# Decoder_35.net
KiCad netlist of a schematic drawn in EAGLE
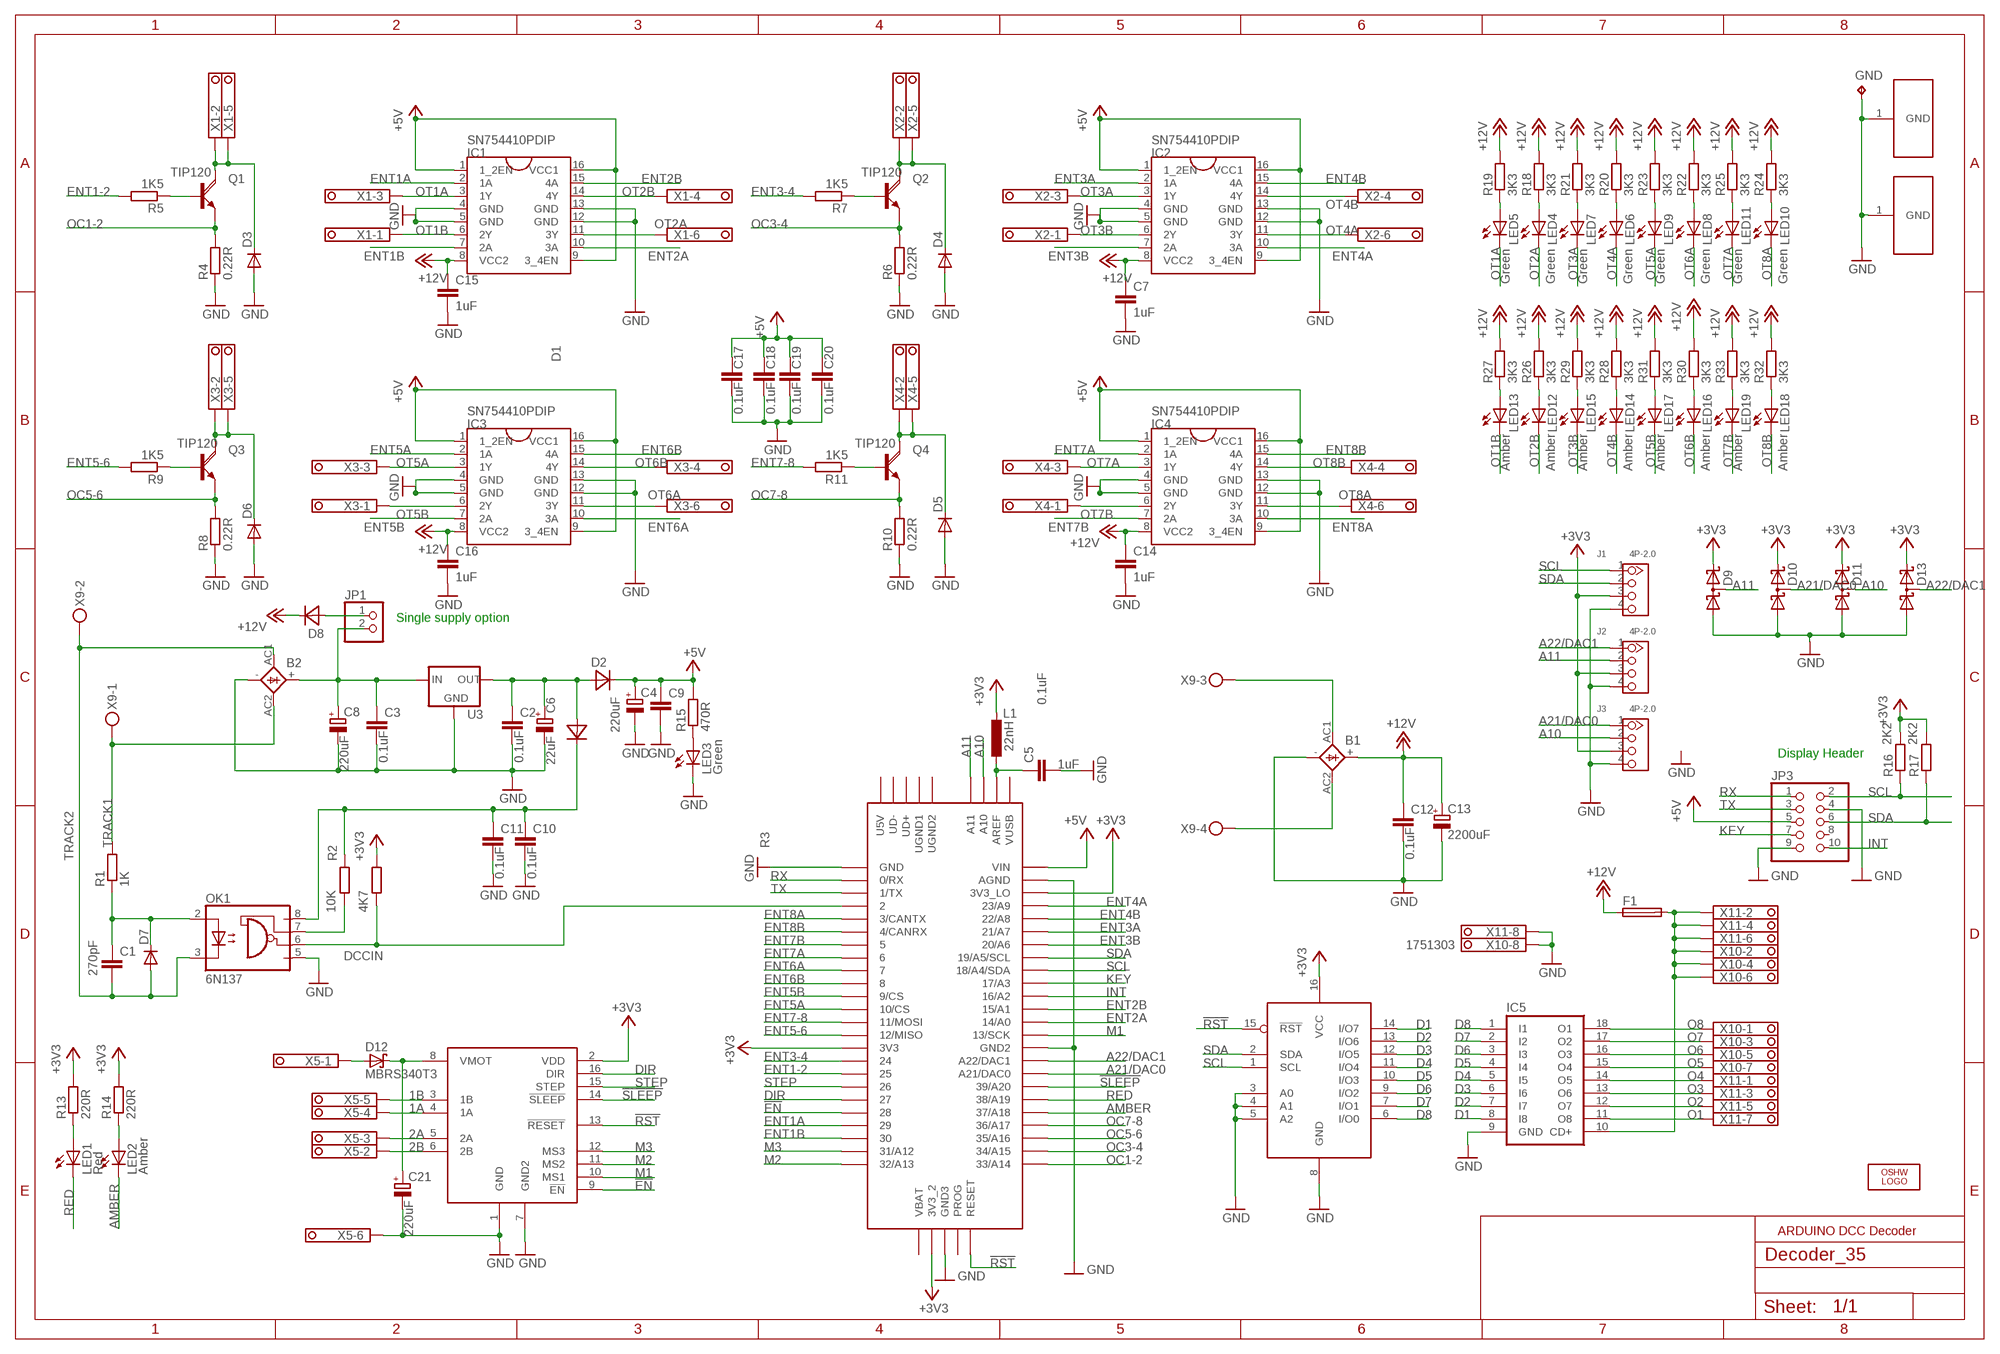
[diagram p0: schematic, sheet 1]

(export (version "E")
  (design (tool "Eeschema 10.0.6"))
  (components
    (comp (ref "B1")
      (value "FB15A")
      (footprint "eagle-import:FB15A")
      (libsource (lib "eagle-import") (part "FB15A"))
    )
    (comp (ref "B2")
      (value "FB15A")
      (footprint "eagle-import:FB15A")
      (libsource (lib "eagle-import") (part "FB15A"))
    )
    (comp (ref "C1")
      (value "270pF")
      (footprint "eagle-import:C0805")
      (libsource (lib "eagle-import") (part "C-EUC0805"))
    )
    (comp (ref "C2")
      (value "0.1uF")
      (footprint "eagle-import:C0805")
      (libsource (lib "eagle-import") (part "C-EUC0805"))
    )
    (comp (ref "C3")
      (value "0.1uF")
      (footprint "eagle-import:C0805")
      (libsource (lib "eagle-import") (part "C-EUC0805"))
    )
    (comp (ref "C4")
      (value "220uF")
      (footprint "eagle-import:E2,5-5")
      (libsource (lib "eagle-import") (part "CPOL-EUE2.5-5"))
    )
    (comp (ref "C5")
      (value "1uF")
      (footprint "eagle-import:C0805")
      (libsource (lib "eagle-import") (part "C-EUC0805"))
    )
    (comp (ref "C6")
      (value "22uF")
      (footprint "eagle-import:E2,5-5")
      (libsource (lib "eagle-import") (part "CPOL-EUE2.5-5"))
    )
    (comp (ref "C7")
      (value "1uF")
      (footprint "eagle-import:C0805")
      (libsource (lib "eagle-import") (part "C-EUC0805"))
    )
    (comp (ref "C8")
      (value "220uF")
      (footprint "eagle-import:E5-8,5")
      (libsource (lib "eagle-import") (part "CPOL-EUE5-8.5"))
    )
    (comp (ref "C9")
      (value "0.1uF")
      (footprint "eagle-import:C0805")
      (libsource (lib "eagle-import") (part "C-EUC0805"))
    )
    (comp (ref "C10")
      (value "0.1uF")
      (footprint "eagle-import:C0805")
      (libsource (lib "eagle-import") (part "C-EUC0805"))
    )
    (comp (ref "C11")
      (value "0.1uF")
      (footprint "eagle-import:C0805")
      (libsource (lib "eagle-import") (part "C-EUC0805"))
    )
    (comp (ref "C12")
      (value "0.1uF")
      (footprint "eagle-import:C0805")
      (libsource (lib "eagle-import") (part "C-EUC0805"))
    )
    (comp (ref "C13")
      (value "2200uF")
      (footprint "eagle-import:E5-13")
      (libsource (lib "eagle-import") (part "CPOL-EUE5-13"))
    )
    (comp (ref "C14")
      (value "1uF")
      (footprint "eagle-import:C0805")
      (libsource (lib "eagle-import") (part "C-EUC0805"))
    )
    (comp (ref "C15")
      (value "1uF")
      (footprint "eagle-import:C0805")
      (libsource (lib "eagle-import") (part "C-EUC0805"))
    )
    (comp (ref "C16")
      (value "1uF")
      (footprint "eagle-import:C0805")
      (libsource (lib "eagle-import") (part "C-EUC0805"))
    )
    (comp (ref "C17")
      (value "0.1uF")
      (footprint "eagle-import:C0805")
      (libsource (lib "eagle-import") (part "C-EUC0805"))
    )
    (comp (ref "C18")
      (value "0.1uF")
      (footprint "eagle-import:C0805")
      (libsource (lib "eagle-import") (part "C-EUC0805"))
    )
    (comp (ref "C19")
      (value "0.1uF")
      (footprint "eagle-import:C0805")
      (libsource (lib "eagle-import") (part "C-EUC0805"))
    )
    (comp (ref "C20")
      (value "0.1uF")
      (footprint "eagle-import:C0805")
      (libsource (lib "eagle-import") (part "C-EUC0805"))
    )
    (comp (ref "C21")
      (value "220uF")
      (footprint "eagle-import:E5-8,5")
      (libsource (lib "eagle-import") (part "CPOL-EUE5-8.5"))
    )
    (comp (ref "D1")
      (value "MBRA340T3")
      (footprint "eagle-import:SMA")
      (libsource (lib "eagle-import") (part "MBRA340T3"))
    )
    (comp (ref "D2")
      (value "MBRA340T3")
      (footprint "eagle-import:SMA")
      (libsource (lib "eagle-import") (part "MBRA340T3"))
    )
    (comp (ref "D3")
      (value "CGRM4002-G")
      (footprint "eagle-import:SOD-123_MINI-SMA")
      (libsource (lib "eagle-import") (part "CGRM400-G2"))
    )
    (comp (ref "D4")
      (value "CGRM4002-G")
      (footprint "eagle-import:SOD-123_MINI-SMA")
      (libsource (lib "eagle-import") (part "CGRM400-G2"))
    )
    (comp (ref "D5")
      (value "CGRM4002-G")
      (footprint "eagle-import:SOD-123_MINI-SMA")
      (libsource (lib "eagle-import") (part "CGRM400-G2"))
    )
    (comp (ref "D6")
      (value "CGRM4002-G")
      (footprint "eagle-import:SOD-123_MINI-SMA")
      (libsource (lib "eagle-import") (part "CGRM400-G2"))
    )
    (comp (ref "D7")
      (value "CGRM4002-G")
      (footprint "eagle-import:SOD-123_MINI-SMA")
      (libsource (lib "eagle-import") (part "CGRM400-G2"))
    )
    (comp (ref "D8")
      (value "MBRA340T3")
      (footprint "eagle-import:SMA")
      (libsource (lib "eagle-import") (part "MBRA340T3"))
    )
    (comp (ref "D9")
      (value "BAS70-04")
      (footprint "eagle-import:SOT23")
      (libsource (lib "eagle-import") (part "BAS70-04"))
    )
    (comp (ref "D10")
      (value "BAS70-04")
      (footprint "eagle-import:SOT23")
      (libsource (lib "eagle-import") (part "BAS70-04"))
    )
    (comp (ref "D11")
      (value "BAS70-04")
      (footprint "eagle-import:SOT23")
      (libsource (lib "eagle-import") (part "BAS70-04"))
    )
    (comp (ref "D12")
      (value "MBRS340T3")
      (footprint "eagle-import:SMC")
      (libsource (lib "eagle-import") (part "MBRS30T34"))
    )
    (comp (ref "D13")
      (value "BAS70-04")
      (footprint "eagle-import:SOT23")
      (libsource (lib "eagle-import") (part "BAS70-04"))
    )
    (comp (ref "F1")
      (value "SMD_FUSE")
      (footprint "eagle-import:1812")
      (fields (field (name "MANUFACTURER") "Littelfuse"))
      (libsource (lib "eagle-import") (part "SMD_FUSE"))
    )
    (comp (ref "GND")
      (value "TPB2,54")
      (footprint "eagle-import:B2,54")
      (libsource (lib "eagle-import") (part "TPB2,54"))
    )
    (comp (ref "IC1")
      (value "SN754410PDIP")
      (footprint "eagle-import:DIL16")
      (libsource (lib "eagle-import") (part "SN754410PDIP"))
    )
    (comp (ref "IC2")
      (value "SN754410PDIP")
      (footprint "eagle-import:DIL16")
      (libsource (lib "eagle-import") (part "SN754410PDIP"))
    )
    (comp (ref "IC3")
      (value "SN754410PDIP")
      (footprint "eagle-import:DIL16")
      (libsource (lib "eagle-import") (part "SN754410PDIP"))
    )
    (comp (ref "IC4")
      (value "SN754410PDIP")
      (footprint "eagle-import:DIL16")
      (libsource (lib "eagle-import") (part "SN754410PDIP"))
    )
    (comp (ref "IC5")
      (value "ULN2803A")
      (footprint "eagle-import:DIL18")
      (libsource (lib "eagle-import") (part "ULN2803A"))
    )
    (comp (ref "J1")
      (value "4P-2.0")
      (footprint "eagle-import:HW4-2.0")
      (libsource (lib "eagle-import") (part "GROVE-CONNECTOR-DIP(4P-2.0)"))
    )
    (comp (ref "J2")
      (value "4P-2.0")
      (footprint "eagle-import:HW4-2.0")
      (libsource (lib "eagle-import") (part "GROVE-CONNECTOR-DIP(4P-2.0)"))
    )
    (comp (ref "J3")
      (value "4P-2.0")
      (footprint "eagle-import:HW4-2.0")
      (libsource (lib "eagle-import") (part "GROVE-CONNECTOR-DIP(4P-2.0)"))
    )
    (comp (ref "JP1")
      (value "PINHD-1X2")
      (footprint "eagle-import:1X02")
      (libsource (lib "eagle-import") (part "PINHD-1X2"))
    )
    (comp (ref "JP3")
      (value "PINHD-2X5")
      (footprint "eagle-import:2X05")
      (libsource (lib "eagle-import") (part "PINHD-2X5"))
    )
    (comp (ref "L1")
      (value "22nH")
      (footprint "eagle-import:L2012C")
      (libsource (lib "eagle-import") (part "L-EUL2012C"))
    )
    (comp (ref "LED1")
      (value "Red")
      (footprint "eagle-import:LED3MM")
      (libsource (lib "eagle-import") (part "LED3MM"))
    )
    (comp (ref "LED2")
      (value "Amber")
      (footprint "eagle-import:LED3MM")
      (libsource (lib "eagle-import") (part "LED3MM"))
    )
    (comp (ref "LED3")
      (value "Green")
      (footprint "eagle-import:LED3MM")
      (libsource (lib "eagle-import") (part "LED3MM"))
    )
    (comp (ref "LED4")
      (value "Green")
      (footprint "eagle-import:LED3MM")
      (libsource (lib "eagle-import") (part "LED3MM"))
    )
    (comp (ref "LED5")
      (value "Green")
      (footprint "eagle-import:LED3MM")
      (libsource (lib "eagle-import") (part "LED3MM"))
    )
    (comp (ref "LED6")
      (value "Green")
      (footprint "eagle-import:LED3MM")
      (libsource (lib "eagle-import") (part "LED3MM"))
    )
    (comp (ref "LED7")
      (value "Green")
      (footprint "eagle-import:LED3MM")
      (libsource (lib "eagle-import") (part "LED3MM"))
    )
    (comp (ref "LED8")
      (value "Green")
      (footprint "eagle-import:LED3MM")
      (libsource (lib "eagle-import") (part "LED3MM"))
    )
    (comp (ref "LED9")
      (value "Green")
      (footprint "eagle-import:LED3MM")
      (libsource (lib "eagle-import") (part "LED3MM"))
    )
    (comp (ref "LED10")
      (value "Green")
      (footprint "eagle-import:LED3MM")
      (libsource (lib "eagle-import") (part "LED3MM"))
    )
    (comp (ref "LED11")
      (value "Green")
      (footprint "eagle-import:LED3MM")
      (libsource (lib "eagle-import") (part "LED3MM"))
    )
    (comp (ref "LED12")
      (value "Amber")
      (footprint "eagle-import:LED3MM")
      (libsource (lib "eagle-import") (part "LED3MM"))
    )
    (comp (ref "LED13")
      (value "Amber")
      (footprint "eagle-import:LED3MM")
      (libsource (lib "eagle-import") (part "LED3MM"))
    )
    (comp (ref "LED14")
      (value "Amber")
      (footprint "eagle-import:LED3MM")
      (libsource (lib "eagle-import") (part "LED3MM"))
    )
    (comp (ref "LED15")
      (value "Amber")
      (footprint "eagle-import:LED3MM")
      (libsource (lib "eagle-import") (part "LED3MM"))
    )
    (comp (ref "LED16")
      (value "Amber")
      (footprint "eagle-import:LED3MM")
      (libsource (lib "eagle-import") (part "LED3MM"))
    )
    (comp (ref "LED17")
      (value "Amber")
      (footprint "eagle-import:LED3MM")
      (libsource (lib "eagle-import") (part "LED3MM"))
    )
    (comp (ref "LED18")
      (value "Amber")
      (footprint "eagle-import:LED3MM")
      (libsource (lib "eagle-import") (part "LED3MM"))
    )
    (comp (ref "LED19")
      (value "Amber")
      (footprint "eagle-import:LED3MM")
      (libsource (lib "eagle-import") (part "LED3MM"))
    )
    (comp (ref "LOGO1")
      (value "OSHW_LOGO_6MILX0200-NT")
      (footprint "eagle-import:OSHW_6X200_NOTEXT")
      (libsource (lib "eagle-import") (part "OSHW_LOGO_6MILX0200-NT"))
    )
    (comp (ref "MT1")
      (value "DINC45_MOUNT")
      (footprint "eagle-import:DIN_C45")
      (libsource (lib "eagle-import") (part "DINC45_MOUNT"))
    )
    (comp (ref "MT2")
      (value "DINC45_MOUNT")
      (footprint "eagle-import:DIN_C45")
      (libsource (lib "eagle-import") (part "DINC45_MOUNT"))
    )
    (comp (ref "OK1")
      (value "6N137")
      (footprint "eagle-import:DIL08")
      (libsource (lib "eagle-import") (part "6N137"))
    )
    (comp (ref "Q1")
      (value "TIP120")
      (footprint "eagle-import:TO220AH")
      (libsource (lib "eagle-import") (part "TIP120"))
    )
    (comp (ref "Q2")
      (value "TIP120")
      (footprint "eagle-import:TO220AH")
      (libsource (lib "eagle-import") (part "TIP120"))
    )
    (comp (ref "Q3")
      (value "TIP120")
      (footprint "eagle-import:TO220AH")
      (libsource (lib "eagle-import") (part "TIP120"))
    )
    (comp (ref "Q4")
      (value "TIP120")
      (footprint "eagle-import:TO220AH")
      (libsource (lib "eagle-import") (part "TIP120"))
    )
    (comp (ref "R1")
      (value "1K")
      (footprint "eagle-import:R0805")
      (libsource (lib "eagle-import") (part "R-EU_R0805"))
    )
    (comp (ref "R2")
      (value "10K")
      (footprint "eagle-import:R0805")
      (libsource (lib "eagle-import") (part "R-EU_R0805"))
    )
    (comp (ref "R3")
      (value "4K7")
      (footprint "eagle-import:R0805")
      (libsource (lib "eagle-import") (part "R-EU_R0805"))
    )
    (comp (ref "R4")
      (value "0.22R")
      (footprint "eagle-import:R2512")
      (libsource (lib "eagle-import") (part "R-EU_R2512"))
    )
    (comp (ref "R5")
      (value "1K5")
      (footprint "eagle-import:R0805")
      (libsource (lib "eagle-import") (part "R-EU_R0805"))
    )
    (comp (ref "R6")
      (value "0.22R")
      (footprint "eagle-import:R2512")
      (libsource (lib "eagle-import") (part "R-EU_R2512"))
    )
    (comp (ref "R7")
      (value "1K5")
      (footprint "eagle-import:R0805")
      (libsource (lib "eagle-import") (part "R-EU_R0805"))
    )
    (comp (ref "R8")
      (value "0.22R")
      (footprint "eagle-import:R2512")
      (libsource (lib "eagle-import") (part "R-EU_R2512"))
    )
    (comp (ref "R9")
      (value "1K5")
      (footprint "eagle-import:R0805")
      (libsource (lib "eagle-import") (part "R-EU_R0805"))
    )
    (comp (ref "R10")
      (value "0.22R")
      (footprint "eagle-import:R2512")
      (libsource (lib "eagle-import") (part "R-EU_R2512"))
    )
    (comp (ref "R11")
      (value "1K5")
      (footprint "eagle-import:R0805")
      (libsource (lib "eagle-import") (part "R-EU_R0805"))
    )
    (comp (ref "R13")
      (value "220R")
      (footprint "eagle-import:R0805")
      (libsource (lib "eagle-import") (part "R-EU_R0805"))
    )
    (comp (ref "R14")
      (value "220R")
      (footprint "eagle-import:R0805")
      (libsource (lib "eagle-import") (part "R-EU_R0805"))
    )
    (comp (ref "R15")
      (value "470R")
      (footprint "eagle-import:R0805")
      (libsource (lib "eagle-import") (part "R-EU_R0805"))
    )
    (comp (ref "R16")
      (value "2K2")
      (footprint "eagle-import:R0805")
      (libsource (lib "eagle-import") (part "R-EU_R0805"))
    )
    (comp (ref "R17")
      (value "2K2")
      (footprint "eagle-import:R0805")
      (libsource (lib "eagle-import") (part "R-EU_R0805"))
    )
    (comp (ref "R18")
      (value "3K3")
      (footprint "eagle-import:R0805")
      (libsource (lib "eagle-import") (part "R-EU_R0805"))
    )
    (comp (ref "R19")
      (value "3K3")
      (footprint "eagle-import:R0805")
      (libsource (lib "eagle-import") (part "R-EU_R0805"))
    )
    (comp (ref "R20")
      (value "3K3")
      (footprint "eagle-import:R0805")
      (libsource (lib "eagle-import") (part "R-EU_R0805"))
    )
    (comp (ref "R21")
      (value "3K3")
      (footprint "eagle-import:R0805")
      (libsource (lib "eagle-import") (part "R-EU_R0805"))
    )
    (comp (ref "R22")
      (value "3K3")
      (footprint "eagle-import:R0805")
      (libsource (lib "eagle-import") (part "R-EU_R0805"))
    )
    (comp (ref "R23")
      (value "3K3")
      (footprint "eagle-import:R0805")
      (libsource (lib "eagle-import") (part "R-EU_R0805"))
    )
    (comp (ref "R24")
      (value "3K3")
      (footprint "eagle-import:R0805")
      (libsource (lib "eagle-import") (part "R-EU_R0805"))
    )
    (comp (ref "R25")
      (value "3K3")
      (footprint "eagle-import:R0805")
      (libsource (lib "eagle-import") (part "R-EU_R0805"))
    )
    (comp (ref "R26")
      (value "3K3")
      (footprint "eagle-import:R0805")
      (libsource (lib "eagle-import") (part "R-EU_R0805"))
    )
    (comp (ref "R27")
      (value "3K3")
      (footprint "eagle-import:R0805")
      (libsource (lib "eagle-import") (part "R-EU_R0805"))
    )
    (comp (ref "R28")
      (value "3K3")
      (footprint "eagle-import:R0805")
      (libsource (lib "eagle-import") (part "R-EU_R0805"))
    )
    (comp (ref "R29")
      (value "3K3")
      (footprint "eagle-import:R0805")
      (libsource (lib "eagle-import") (part "R-EU_R0805"))
    )
    (comp (ref "R30")
      (value "3K3")
      (footprint "eagle-import:R0805")
      (libsource (lib "eagle-import") (part "R-EU_R0805"))
    )
    (comp (ref "R31")
      (value "3K3")
      (footprint "eagle-import:R0805")
      (libsource (lib "eagle-import") (part "R-EU_R0805"))
    )
    (comp (ref "R32")
      (value "3K3")
      (footprint "eagle-import:R0805")
      (libsource (lib "eagle-import") (part "R-EU_R0805"))
    )
    (comp (ref "R33")
      (value "3K3")
      (footprint "eagle-import:R0805")
      (libsource (lib "eagle-import") (part "R-EU_R0805"))
    )
    (comp (ref "U$1")
      (value "TEENSY_3.5/3.6")
      (footprint "eagle-import:TEENSY_3.5_3.6")
      (libsource (lib "eagle-import") (part "TEENSY_3.5/3.6"))
    )
    (comp (ref "U1")
      (value "A4988")
      (footprint "eagle-import:POLOLUA4988")
      (libsource (lib "eagle-import") (part "A4988"))
    )
    (comp (ref "U2")
      (value "PCA9557")
      (footprint "eagle-import:S016")
      (libsource (lib "eagle-import") (part "PCA9557"))
    )
    (comp (ref "U3")
      (value "V_REG_78XX-TO-220")
      (footprint "eagle-import:TO-220-ALT")
      (libsource (lib "eagle-import") (part "V_REG_78XX-TO-220"))
    )
    (comp (ref "X1")
      (value "1751280")
      (footprint "eagle-import:1751280")
      (libsource (lib "eagle-import") (part "1751280"))
    )
    (comp (ref "X2")
      (value "1751280")
      (footprint "eagle-import:1751280")
      (libsource (lib "eagle-import") (part "1751280"))
    )
    (comp (ref "X3")
      (value "1751280")
      (footprint "eagle-import:1751280")
      (libsource (lib "eagle-import") (part "1751280"))
    )
    (comp (ref "X4")
      (value "1751280")
      (footprint "eagle-import:1751280")
      (libsource (lib "eagle-import") (part "1751280"))
    )
    (comp (ref "X5")
      (value "1751280")
      (footprint "eagle-import:1751280")
      (libsource (lib "eagle-import") (part "1751280"))
    )
    (comp (ref "X9")
      (value "MKDSN1,5/4-5,08")
      (footprint "eagle-import:MKDSN1,5_4-5,08")
      (libsource (lib "eagle-import") (part "MKDSN1,5/4-5,08"))
    )
    (comp (ref "X10")
      (value "1751303")
      (footprint "eagle-import:1751303")
      (libsource (lib "eagle-import") (part "1751303"))
    )
    (comp (ref "X11")
      (value "1751303")
      (footprint "eagle-import:1751303")
      (libsource (lib "eagle-import") (part "1751303"))
    )
  )
  (nets
    (net (code "1") (name "+3V3") (class "Default")
      (node (ref "D10") (pin "2") (pinfunction "C2_2") (pintype "passive"))
      (node (ref "D11") (pin "2") (pinfunction "C2_2") (pintype "passive"))
      (node (ref "D13") (pin "2") (pinfunction "C2_2") (pintype "passive"))
      (node (ref "D9") (pin "2") (pinfunction "C2_2") (pintype "passive"))
      (node (ref "J1") (pin "3") (pinfunction "3_3") (pintype "bidirectional"))
      (node (ref "J2") (pin "3") (pinfunction "3_3") (pintype "bidirectional"))
      (node (ref "J3") (pin "3") (pinfunction "3_3") (pintype "bidirectional"))
      (node (ref "L1") (pin "1") (pinfunction "1_1") (pintype "passive"))
      (node (ref "R13") (pin "2") (pinfunction "2_2") (pintype "passive"))
      (node (ref "R14") (pin "2") (pinfunction "2_2") (pintype "passive"))
      (node (ref "R16") (pin "2") (pinfunction "2_2") (pintype "passive"))
      (node (ref "R17") (pin "2") (pinfunction "2_2") (pintype "passive"))
      (node (ref "R3") (pin "2") (pinfunction "2_2") (pintype "passive"))
      (node (ref "U$1") (pin "3V3") (pinfunction "3V3_3V3") (pintype "bidirectional"))
      (node (ref "U$1") (pin "3V3_2") (pinfunction "3V3_2_3V3_2") (pintype "bidirectional"))
      (node (ref "U$1") (pin "3V3_LO") (pinfunction "3V3_LO_3V3_LO") (pintype "bidirectional"))
      (node (ref "U1") (pin "2") (pinfunction "VDD_2") (pintype "power_in"))
      (node (ref "U2") (pin "16") (pinfunction "VCC_16") (pintype "power_in"))
    )
    (net (code "2") (name "+5V") (class "Default")
      (node (ref "C17") (pin "1") (pinfunction "1_1") (pintype "passive"))
      (node (ref "C18") (pin "1") (pinfunction "1_1") (pintype "passive"))
      (node (ref "C19") (pin "1") (pinfunction "1_1") (pintype "passive"))
      (node (ref "C20") (pin "1") (pinfunction "1_1") (pintype "passive"))
      (node (ref "C4") (pin "+") (pinfunction "+_+") (pintype "passive"))
      (node (ref "C9") (pin "1") (pinfunction "1_1") (pintype "passive"))
      (node (ref "D2") (pin "C") (pinfunction "C_C") (pintype "passive"))
      (node (ref "IC1") (pin "1") (pinfunction "1_2EN_1") (pintype "bidirectional"))
      (node (ref "IC1") (pin "16") (pinfunction "VCC1_16") (pintype "bidirectional"))
      (node (ref "IC1") (pin "9") (pinfunction "3_4EN_9") (pintype "bidirectional"))
      (node (ref "IC2") (pin "1") (pinfunction "1_2EN_1") (pintype "bidirectional"))
      (node (ref "IC2") (pin "16") (pinfunction "VCC1_16") (pintype "bidirectional"))
      (node (ref "IC2") (pin "9") (pinfunction "3_4EN_9") (pintype "bidirectional"))
      (node (ref "IC3") (pin "1") (pinfunction "1_2EN_1") (pintype "bidirectional"))
      (node (ref "IC3") (pin "16") (pinfunction "VCC1_16") (pintype "bidirectional"))
      (node (ref "IC3") (pin "9") (pinfunction "3_4EN_9") (pintype "bidirectional"))
      (node (ref "IC4") (pin "1") (pinfunction "1_2EN_1") (pintype "bidirectional"))
      (node (ref "IC4") (pin "16") (pinfunction "VCC1_16") (pintype "bidirectional"))
      (node (ref "IC4") (pin "9") (pinfunction "3_4EN_9") (pintype "bidirectional"))
      (node (ref "JP3") (pin "5") (pinfunction "5_5") (pintype "passive"))
      (node (ref "R15") (pin "2") (pinfunction "2_2") (pintype "passive"))
      (node (ref "U$1") (pin "VIN") (pinfunction "VIN_VIN") (pintype "bidirectional"))
    )
    (net (code "3") (name "+12V") (class "Default")
      (node (ref "B1") (pin "+") (pinfunction "+_+") (pintype "passive"))
      (node (ref "C12") (pin "1") (pinfunction "1_1") (pintype "passive"))
      (node (ref "C13") (pin "+") (pinfunction "+_+") (pintype "passive"))
      (node (ref "C14") (pin "1") (pinfunction "1_1") (pintype "passive"))
      (node (ref "C15") (pin "1") (pinfunction "1_1") (pintype "passive"))
      (node (ref "C16") (pin "1") (pinfunction "1_1") (pintype "passive"))
      (node (ref "C7") (pin "1") (pinfunction "1_1") (pintype "passive"))
      (node (ref "D8") (pin "C") (pinfunction "C_C") (pintype "passive"))
      (node (ref "F1") (pin "1") (pinfunction "1_1") (pintype "passive"))
      (node (ref "IC1") (pin "8") (pinfunction "VCC2_8") (pintype "bidirectional"))
      (node (ref "IC2") (pin "8") (pinfunction "VCC2_8") (pintype "bidirectional"))
      (node (ref "IC3") (pin "8") (pinfunction "VCC2_8") (pintype "bidirectional"))
      (node (ref "IC4") (pin "8") (pinfunction "VCC2_8") (pintype "bidirectional"))
      (node (ref "R18") (pin "2") (pinfunction "2_2") (pintype "passive"))
      (node (ref "R19") (pin "2") (pinfunction "2_2") (pintype "passive"))
      (node (ref "R20") (pin "2") (pinfunction "2_2") (pintype "passive"))
      (node (ref "R21") (pin "2") (pinfunction "2_2") (pintype "passive"))
      (node (ref "R22") (pin "2") (pinfunction "2_2") (pintype "passive"))
      (node (ref "R23") (pin "2") (pinfunction "2_2") (pintype "passive"))
      (node (ref "R24") (pin "2") (pinfunction "2_2") (pintype "passive"))
      (node (ref "R25") (pin "2") (pinfunction "2_2") (pintype "passive"))
      (node (ref "R26") (pin "2") (pinfunction "2_2") (pintype "passive"))
      (node (ref "R27") (pin "2") (pinfunction "2_2") (pintype "passive"))
      (node (ref "R28") (pin "2") (pinfunction "2_2") (pintype "passive"))
      (node (ref "R29") (pin "2") (pinfunction "2_2") (pintype "passive"))
      (node (ref "R30") (pin "2") (pinfunction "2_2") (pintype "passive"))
      (node (ref "R31") (pin "2") (pinfunction "2_2") (pintype "passive"))
      (node (ref "R32") (pin "2") (pinfunction "2_2") (pintype "passive"))
      (node (ref "R33") (pin "2") (pinfunction "2_2") (pintype "passive"))
    )
    (net (code "4") (name "/1A") (class "Default")
      (node (ref "U1") (pin "4") (pinfunction "1A_4") (pintype "open_collector"))
      (node (ref "X5") (pin "4") (pinfunction "K_4") (pintype "passive"))
    )
    (net (code "5") (name "/1B") (class "Default")
      (node (ref "U1") (pin "3") (pinfunction "1B_3") (pintype "open_collector"))
      (node (ref "X5") (pin "5") (pinfunction "K_5") (pintype "passive"))
    )
    (net (code "6") (name "/2A") (class "Default")
      (node (ref "U1") (pin "5") (pinfunction "2A_5") (pintype "open_collector"))
      (node (ref "X5") (pin "3") (pinfunction "K_3") (pintype "passive"))
    )
    (net (code "7") (name "/2B") (class "Default")
      (node (ref "U1") (pin "6") (pinfunction "2B_6") (pintype "open_collector"))
      (node (ref "X5") (pin "2") (pinfunction "K_2") (pintype "passive"))
    )
    (net (code "8") (name "/A10") (class "Default")
      (node (ref "D11") (pin "3") (pinfunction "C1A2_3") (pintype "passive"))
      (node (ref "J3") (pin "2") (pinfunction "2_2") (pintype "bidirectional"))
      (node (ref "U$1") (pin "A10") (pinfunction "A10_A10") (pintype "bidirectional"))
    )
    (net (code "9") (name "/A11") (class "Default")
      (node (ref "D9") (pin "3") (pinfunction "C1A2_3") (pintype "passive"))
      (node (ref "J2") (pin "2") (pinfunction "2_2") (pintype "bidirectional"))
      (node (ref "U$1") (pin "A11") (pinfunction "A11_A11") (pintype "bidirectional"))
    )
    (net (code "10") (name "/A21{slash}DAC0") (class "Default")
      (node (ref "D10") (pin "3") (pinfunction "C1A2_3") (pintype "passive"))
      (node (ref "J3") (pin "1") (pinfunction "1_1") (pintype "bidirectional"))
      (node (ref "U$1") (pin "21/DAC0") (pinfunction "A21/DAC0_21/DAC0") (pintype "bidirectional"))
    )
    (net (code "11") (name "/A22{slash}DAC1") (class "Default")
      (node (ref "D13") (pin "3") (pinfunction "C1A2_3") (pintype "passive"))
      (node (ref "J2") (pin "1") (pinfunction "1_1") (pintype "bidirectional"))
      (node (ref "U$1") (pin "A22/DAC1") (pinfunction "A22/DAC1_A22/DAC1") (pintype "bidirectional"))
    )
    (net (code "12") (name "/AMBER") (class "Default")
      (node (ref "LED2") (pin "K") (pinfunction "C_K") (pintype "passive"))
      (node (ref "U$1") (pin "37/A18") (pinfunction "37/A18_37/A18") (pintype "bidirectional"))
    )
    (net (code "13") (name "/D1") (class "Default")
      (node (ref "IC5") (pin "8") (pinfunction "I8_8") (pintype "input"))
      (node (ref "U2") (pin "14") (pinfunction "I/O7_14") (pintype "bidirectional"))
    )
    (net (code "14") (name "/D2") (class "Default")
      (node (ref "IC5") (pin "7") (pinfunction "I7_7") (pintype "input"))
      (node (ref "U2") (pin "13") (pinfunction "I/O6_13") (pintype "bidirectional"))
    )
    (net (code "15") (name "/D3") (class "Default")
      (node (ref "IC5") (pin "6") (pinfunction "I6_6") (pintype "input"))
      (node (ref "U2") (pin "12") (pinfunction "I/O5_12") (pintype "bidirectional"))
    )
    (net (code "16") (name "/D4") (class "Default")
      (node (ref "IC5") (pin "5") (pinfunction "I5_5") (pintype "input"))
      (node (ref "U2") (pin "11") (pinfunction "I/O4_11") (pintype "bidirectional"))
    )
    (net (code "17") (name "/D5") (class "Default")
      (node (ref "IC5") (pin "4") (pinfunction "I4_4") (pintype "input"))
      (node (ref "U2") (pin "10") (pinfunction "I/O3_10") (pintype "bidirectional"))
    )
    (net (code "18") (name "/D6") (class "Default")
      (node (ref "IC5") (pin "3") (pinfunction "I3_3") (pintype "input"))
      (node (ref "U2") (pin "9") (pinfunction "I/O2_9") (pintype "bidirectional"))
    )
    (net (code "19") (name "/D7") (class "Default")
      (node (ref "IC5") (pin "2") (pinfunction "I2_2") (pintype "input"))
      (node (ref "U2") (pin "7") (pinfunction "I/O1_7") (pintype "bidirectional"))
    )
    (net (code "20") (name "/D8") (class "Default")
      (node (ref "IC5") (pin "1") (pinfunction "I1_1") (pintype "input"))
      (node (ref "U2") (pin "6") (pinfunction "I/O0_6") (pintype "bidirectional"))
    )
    (net (code "21") (name "/DCCIN") (class "Default")
      (node (ref "OK1") (pin "6") (pinfunction "VO_6") (pintype "passive"))
      (node (ref "R3") (pin "1") (pinfunction "1_1") (pintype "passive"))
      (node (ref "U$1") (pin "2") (pinfunction "2_2") (pintype "bidirectional"))
    )
    (net (code "22") (name "/DIR") (class "Default")
      (node (ref "U$1") (pin "27") (pinfunction "27_27") (pintype "bidirectional"))
      (node (ref "U1") (pin "16") (pinfunction "DIR_16") (pintype "input"))
    )
    (net (code "23") (name "/ENT1-2") (class "Default")
      (node (ref "R5") (pin "2") (pinfunction "2_2") (pintype "passive"))
      (node (ref "U$1") (pin "25") (pinfunction "25_25") (pintype "bidirectional"))
    )
    (net (code "24") (name "/ENT1A") (class "Default")
      (node (ref "IC1") (pin "2") (pinfunction "1A_2") (pintype "bidirectional"))
      (node (ref "U$1") (pin "29") (pinfunction "29_29") (pintype "bidirectional"))
    )
    (net (code "25") (name "/ENT1B") (class "Default")
      (node (ref "IC1") (pin "7") (pinfunction "2A_7") (pintype "bidirectional"))
      (node (ref "U$1") (pin "30") (pinfunction "30_30") (pintype "bidirectional"))
    )
    (net (code "26") (name "/ENT2A") (class "Default")
      (node (ref "IC1") (pin "10") (pinfunction "3A_10") (pintype "bidirectional"))
      (node (ref "U$1") (pin "14/A0") (pinfunction "14/A0_14/A0") (pintype "bidirectional"))
    )
    (net (code "27") (name "/ENT2B") (class "Default")
      (node (ref "IC1") (pin "15") (pinfunction "4A_15") (pintype "bidirectional"))
      (node (ref "U$1") (pin "15/A1") (pinfunction "15/A1_15/A1") (pintype "bidirectional"))
    )
    (net (code "28") (name "/ENT3-4") (class "Default")
      (node (ref "R7") (pin "2") (pinfunction "2_2") (pintype "passive"))
      (node (ref "U$1") (pin "24") (pinfunction "24_24") (pintype "bidirectional"))
    )
    (net (code "29") (name "/ENT3A") (class "Default")
      (node (ref "IC2") (pin "2") (pinfunction "1A_2") (pintype "bidirectional"))
      (node (ref "U$1") (pin "21/A7") (pinfunction "21/A7_21/A7") (pintype "bidirectional"))
    )
    (net (code "30") (name "/ENT3B") (class "Default")
      (node (ref "IC2") (pin "7") (pinfunction "2A_7") (pintype "bidirectional"))
      (node (ref "U$1") (pin "20/A6") (pinfunction "20/A6_20/A6") (pintype "bidirectional"))
    )
    (net (code "31") (name "/ENT4A") (class "Default")
      (node (ref "IC2") (pin "10") (pinfunction "3A_10") (pintype "bidirectional"))
      (node (ref "U$1") (pin "23/A9") (pinfunction "23/A9_23/A9") (pintype "bidirectional"))
    )
    (net (code "32") (name "/ENT4B") (class "Default")
      (node (ref "IC2") (pin "15") (pinfunction "4A_15") (pintype "bidirectional"))
      (node (ref "U$1") (pin "22/A8") (pinfunction "22/A8_22/A8") (pintype "bidirectional"))
    )
    (net (code "33") (name "/ENT5-6") (class "Default")
      (node (ref "R9") (pin "2") (pinfunction "2_2") (pintype "passive"))
      (node (ref "U$1") (pin "12/MISO") (pinfunction "12/MISO_12/MISO") (pintype "bidirectional"))
    )
    (net (code "34") (name "/ENT5A") (class "Default")
      (node (ref "IC3") (pin "2") (pinfunction "1A_2") (pintype "bidirectional"))
      (node (ref "U$1") (pin "10/CS") (pinfunction "10/CS_10/CS") (pintype "bidirectional"))
    )
    (net (code "35") (name "/ENT5B") (class "Default")
      (node (ref "IC3") (pin "7") (pinfunction "2A_7") (pintype "bidirectional"))
      (node (ref "U$1") (pin "9/CS") (pinfunction "9/CS_9/CS") (pintype "bidirectional"))
    )
    (net (code "36") (name "/ENT6A") (class "Default")
      (node (ref "IC3") (pin "10") (pinfunction "3A_10") (pintype "bidirectional"))
      (node (ref "U$1") (pin "7") (pinfunction "7_7") (pintype "bidirectional"))
    )
    (net (code "37") (name "/ENT6B") (class "Default")
      (node (ref "IC3") (pin "15") (pinfunction "4A_15") (pintype "bidirectional"))
      (node (ref "U$1") (pin "8") (pinfunction "8_8") (pintype "bidirectional"))
    )
    (net (code "38") (name "/ENT7-8") (class "Default")
      (node (ref "R11") (pin "2") (pinfunction "2_2") (pintype "passive"))
      (node (ref "U$1") (pin "11/MOSI") (pinfunction "11/MOSI_11/MOSI") (pintype "bidirectional"))
    )
    (net (code "39") (name "/ENT7A") (class "Default")
      (node (ref "IC4") (pin "2") (pinfunction "1A_2") (pintype "bidirectional"))
      (node (ref "U$1") (pin "6") (pinfunction "6_6") (pintype "bidirectional"))
    )
    (net (code "40") (name "/ENT7B") (class "Default")
      (node (ref "IC4") (pin "7") (pinfunction "2A_7") (pintype "bidirectional"))
      (node (ref "U$1") (pin "5") (pinfunction "5_5") (pintype "bidirectional"))
    )
    (net (code "41") (name "/ENT8A") (class "Default")
      (node (ref "IC4") (pin "10") (pinfunction "3A_10") (pintype "bidirectional"))
      (node (ref "U$1") (pin "3/CANTX") (pinfunction "3/CANTX_3/CANTX") (pintype "bidirectional"))
    )
    (net (code "42") (name "/ENT8B") (class "Default")
      (node (ref "IC4") (pin "15") (pinfunction "4A_15") (pintype "bidirectional"))
      (node (ref "U$1") (pin "4/CANRX") (pinfunction "4/CANRX_4/CANRX") (pintype "bidirectional"))
    )
    (net (code "43") (name "/INT") (class "Default")
      (node (ref "JP3") (pin "10") (pinfunction "10_10") (pintype "passive"))
      (node (ref "U$1") (pin "16/A2") (pinfunction "16/A2_16/A2") (pintype "bidirectional"))
    )
    (net (code "44") (name "/KEY") (class "Default")
      (node (ref "JP3") (pin "7") (pinfunction "7_7") (pintype "passive"))
      (node (ref "U$1") (pin "17/A3") (pinfunction "17/A3_17/A3") (pintype "bidirectional"))
    )
    (net (code "45") (name "/M1") (class "Default")
      (node (ref "U$1") (pin "13/SCK") (pinfunction "13/SCK_13/SCK") (pintype "bidirectional"))
      (node (ref "U1") (pin "10") (pinfunction "MS1_10") (pintype "input"))
    )
    (net (code "46") (name "/M2") (class "Default")
      (node (ref "U$1") (pin "32/A13") (pinfunction "32/A13_32/A13") (pintype "bidirectional"))
      (node (ref "U1") (pin "11") (pinfunction "MS2_11") (pintype "input"))
    )
    (net (code "47") (name "/M3") (class "Default")
      (node (ref "U$1") (pin "31/A12") (pinfunction "31/A12_31/A12") (pintype "bidirectional"))
      (node (ref "U1") (pin "12") (pinfunction "MS3_12") (pintype "input"))
    )
    (net (code "48") (name "/O1") (class "Default")
      (node (ref "IC5") (pin "11") (pinfunction "O8_11") (pintype "open_collector"))
      (node (ref "X11") (pin "7") (pinfunction "K_7") (pintype "passive"))
    )
    (net (code "49") (name "/O2") (class "Default")
      (node (ref "IC5") (pin "12") (pinfunction "O7_12") (pintype "open_collector"))
      (node (ref "X11") (pin "5") (pinfunction "K_5") (pintype "passive"))
    )
    (net (code "50") (name "/O3") (class "Default")
      (node (ref "IC5") (pin "13") (pinfunction "O6_13") (pintype "open_collector"))
      (node (ref "X11") (pin "3") (pinfunction "K_3") (pintype "passive"))
    )
    (net (code "51") (name "/O4") (class "Default")
      (node (ref "IC5") (pin "14") (pinfunction "O5_14") (pintype "open_collector"))
      (node (ref "X11") (pin "1") (pinfunction "K_1") (pintype "passive"))
    )
    (net (code "52") (name "/O5") (class "Default")
      (node (ref "IC5") (pin "15") (pinfunction "O4_15") (pintype "open_collector"))
      (node (ref "X10") (pin "7") (pinfunction "K_7") (pintype "passive"))
    )
    (net (code "53") (name "/O6") (class "Default")
      (node (ref "IC5") (pin "16") (pinfunction "O3_16") (pintype "open_collector"))
      (node (ref "X10") (pin "5") (pinfunction "K_5") (pintype "passive"))
    )
    (net (code "54") (name "/O7") (class "Default")
      (node (ref "IC5") (pin "17") (pinfunction "O2_17") (pintype "open_collector"))
      (node (ref "X10") (pin "3") (pinfunction "K_3") (pintype "passive"))
    )
    (net (code "55") (name "/O8") (class "Default")
      (node (ref "IC5") (pin "18") (pinfunction "O1_18") (pintype "open_collector"))
      (node (ref "X10") (pin "1") (pinfunction "K_1") (pintype "passive"))
    )
    (net (code "56") (name "/OC1-2") (class "Default")
      (node (ref "Q1") (pin "E") (pinfunction "E_E") (pintype "passive"))
      (node (ref "R4") (pin "2") (pinfunction "2_2") (pintype "passive"))
      (node (ref "U$1") (pin "33/A14") (pinfunction "33/A14_33/A14") (pintype "bidirectional"))
    )
    (net (code "57") (name "/OC3-4") (class "Default")
      (node (ref "Q2") (pin "E") (pinfunction "E_E") (pintype "passive"))
      (node (ref "R6") (pin "2") (pinfunction "2_2") (pintype "passive"))
      (node (ref "U$1") (pin "34/A15") (pinfunction "34/A15_34/A15") (pintype "bidirectional"))
    )
    (net (code "58") (name "/OC5-6") (class "Default")
      (node (ref "Q3") (pin "E") (pinfunction "E_E") (pintype "passive"))
      (node (ref "R8") (pin "2") (pinfunction "2_2") (pintype "passive"))
      (node (ref "U$1") (pin "35/A16") (pinfunction "35/A16_35/A16") (pintype "bidirectional"))
    )
    (net (code "59") (name "/OC7-8") (class "Default")
      (node (ref "Q4") (pin "E") (pinfunction "E_E") (pintype "passive"))
      (node (ref "R10") (pin "2") (pinfunction "2_2") (pintype "passive"))
      (node (ref "U$1") (pin "36/A17") (pinfunction "36/A17_36/A17") (pintype "bidirectional"))
    )
    (net (code "60") (name "/OT1A") (class "Default")
      (node (ref "IC1") (pin "3") (pinfunction "1Y_3") (pintype "bidirectional"))
      (node (ref "LED5") (pin "K") (pinfunction "C_K") (pintype "passive"))
      (node (ref "X1") (pin "3") (pinfunction "K_3") (pintype "passive"))
    )
    (net (code "61") (name "/OT1B") (class "Default")
      (node (ref "IC1") (pin "6") (pinfunction "2Y_6") (pintype "bidirectional"))
      (node (ref "LED13") (pin "K") (pinfunction "C_K") (pintype "passive"))
      (node (ref "X1") (pin "1") (pinfunction "K_1") (pintype "passive"))
    )
    (net (code "62") (name "/OT2A") (class "Default")
      (node (ref "IC1") (pin "11") (pinfunction "3Y_11") (pintype "bidirectional"))
      (node (ref "LED4") (pin "K") (pinfunction "C_K") (pintype "passive"))
      (node (ref "X1") (pin "6") (pinfunction "K_6") (pintype "passive"))
    )
    (net (code "63") (name "/OT2B") (class "Default")
      (node (ref "IC1") (pin "14") (pinfunction "4Y_14") (pintype "bidirectional"))
      (node (ref "LED12") (pin "K") (pinfunction "C_K") (pintype "passive"))
      (node (ref "X1") (pin "4") (pinfunction "K_4") (pintype "passive"))
    )
    (net (code "64") (name "/OT3A") (class "Default")
      (node (ref "IC2") (pin "3") (pinfunction "1Y_3") (pintype "bidirectional"))
      (node (ref "LED7") (pin "K") (pinfunction "C_K") (pintype "passive"))
      (node (ref "X2") (pin "3") (pinfunction "K_3") (pintype "passive"))
    )
    (net (code "65") (name "/OT3B") (class "Default")
      (node (ref "IC2") (pin "6") (pinfunction "2Y_6") (pintype "bidirectional"))
      (node (ref "LED15") (pin "K") (pinfunction "C_K") (pintype "passive"))
      (node (ref "X2") (pin "1") (pinfunction "K_1") (pintype "passive"))
    )
    (net (code "66") (name "/OT4A") (class "Default")
      (node (ref "IC2") (pin "11") (pinfunction "3Y_11") (pintype "bidirectional"))
      (node (ref "LED6") (pin "K") (pinfunction "C_K") (pintype "passive"))
      (node (ref "X2") (pin "6") (pinfunction "K_6") (pintype "passive"))
    )
    (net (code "67") (name "/OT4B") (class "Default")
      (node (ref "IC2") (pin "14") (pinfunction "4Y_14") (pintype "bidirectional"))
      (node (ref "LED14") (pin "K") (pinfunction "C_K") (pintype "passive"))
      (node (ref "X2") (pin "4") (pinfunction "K_4") (pintype "passive"))
    )
    (net (code "68") (name "/OT5A") (class "Default")
      (node (ref "IC3") (pin "3") (pinfunction "1Y_3") (pintype "bidirectional"))
      (node (ref "LED9") (pin "K") (pinfunction "C_K") (pintype "passive"))
      (node (ref "X3") (pin "3") (pinfunction "K_3") (pintype "passive"))
    )
    (net (code "69") (name "/OT5B") (class "Default")
      (node (ref "IC3") (pin "6") (pinfunction "2Y_6") (pintype "bidirectional"))
      (node (ref "LED17") (pin "K") (pinfunction "C_K") (pintype "passive"))
      (node (ref "X3") (pin "1") (pinfunction "K_1") (pintype "passive"))
    )
    (net (code "70") (name "/OT6A") (class "Default")
      (node (ref "IC3") (pin "11") (pinfunction "3Y_11") (pintype "bidirectional"))
      (node (ref "LED8") (pin "K") (pinfunction "C_K") (pintype "passive"))
      (node (ref "X3") (pin "6") (pinfunction "K_6") (pintype "passive"))
    )
    (net (code "71") (name "/OT6B") (class "Default")
      (node (ref "IC3") (pin "14") (pinfunction "4Y_14") (pintype "bidirectional"))
      (node (ref "LED16") (pin "K") (pinfunction "C_K") (pintype "passive"))
      (node (ref "X3") (pin "4") (pinfunction "K_4") (pintype "passive"))
    )
    (net (code "72") (name "/OT7A") (class "Default")
      (node (ref "IC4") (pin "3") (pinfunction "1Y_3") (pintype "bidirectional"))
      (node (ref "LED11") (pin "K") (pinfunction "C_K") (pintype "passive"))
      (node (ref "X4") (pin "3") (pinfunction "K_3") (pintype "passive"))
    )
    (net (code "73") (name "/OT7B") (class "Default")
      (node (ref "IC4") (pin "6") (pinfunction "2Y_6") (pintype "bidirectional"))
      (node (ref "LED19") (pin "K") (pinfunction "C_K") (pintype "passive"))
      (node (ref "X4") (pin "1") (pinfunction "K_1") (pintype "passive"))
    )
    (net (code "74") (name "/OT8A") (class "Default")
      (node (ref "IC4") (pin "11") (pinfunction "3Y_11") (pintype "bidirectional"))
      (node (ref "LED10") (pin "K") (pinfunction "C_K") (pintype "passive"))
      (node (ref "X4") (pin "6") (pinfunction "K_6") (pintype "passive"))
    )
    (net (code "75") (name "/OT8B") (class "Default")
      (node (ref "IC4") (pin "14") (pinfunction "4Y_14") (pintype "bidirectional"))
      (node (ref "LED18") (pin "K") (pinfunction "C_K") (pintype "passive"))
      (node (ref "X4") (pin "4") (pinfunction "K_4") (pintype "passive"))
    )
    (net (code "76") (name "/RED") (class "Default")
      (node (ref "LED1") (pin "K") (pinfunction "C_K") (pintype "passive"))
      (node (ref "U$1") (pin "38/A19") (pinfunction "38/A19_38/A19") (pintype "bidirectional"))
    )
    (net (code "77") (name "/RX") (class "Default")
      (node (ref "JP3") (pin "1") (pinfunction "1_1") (pintype "passive"))
      (node (ref "U$1") (pin "0/RX") (pinfunction "0/RX_0/RX") (pintype "bidirectional"))
    )
    (net (code "78") (name "/SCL") (class "Default")
      (node (ref "J1") (pin "1") (pinfunction "1_1") (pintype "bidirectional"))
      (node (ref "JP3") (pin "2") (pinfunction "2_2") (pintype "passive"))
      (node (ref "R16") (pin "1") (pinfunction "1_1") (pintype "passive"))
      (node (ref "U$1") (pin "18/A4/SDA") (pinfunction "18/A4/SDA_18/A4/SDA") (pintype "bidirectional"))
      (node (ref "U2") (pin "1") (pinfunction "SCL_1") (pintype "input"))
    )
    (net (code "79") (name "/SDA") (class "Default")
      (node (ref "J1") (pin "2") (pinfunction "2_2") (pintype "bidirectional"))
      (node (ref "JP3") (pin "6") (pinfunction "6_6") (pintype "passive"))
      (node (ref "R17") (pin "1") (pinfunction "1_1") (pintype "passive"))
      (node (ref "U$1") (pin "19/A5/SCL") (pinfunction "19/A5/SCL_19/A5/SCL") (pintype "bidirectional"))
      (node (ref "U2") (pin "2") (pinfunction "SDA_2") (pintype "bidirectional"))
    )
    (net (code "80") (name "/STEP") (class "Default")
      (node (ref "U$1") (pin "26") (pinfunction "26_26") (pintype "bidirectional"))
      (node (ref "U1") (pin "15") (pinfunction "STEP_15") (pintype "input"))
    )
    (net (code "81") (name "/TRACK1") (class "Default")
      (node (ref "B2") (pin "AC2") (pinfunction "AC2_AC2") (pintype "passive"))
      (node (ref "R1") (pin "2") (pinfunction "2_2") (pintype "passive"))
      (node (ref "X9") (pin "1") (pinfunction "KL_1") (pintype "passive"))
    )
    (net (code "82") (name "/TRACK2") (class "Default")
      (node (ref "B2") (pin "AC1") (pinfunction "AC1_AC1") (pintype "passive"))
      (node (ref "C1") (pin "2") (pinfunction "2_2") (pintype "passive"))
      (node (ref "D7") (pin "A") (pinfunction "A_A") (pintype "passive"))
      (node (ref "OK1") (pin "3") (pinfunction "C_3") (pintype "passive"))
      (node (ref "X9") (pin "2") (pinfunction "KL_2") (pintype "passive"))
    )
    (net (code "83") (name "/TX") (class "Default")
      (node (ref "JP3") (pin "3") (pinfunction "3_3") (pintype "passive"))
      (node (ref "U$1") (pin "1/TX") (pinfunction "1/TX_1/TX") (pintype "bidirectional"))
    )
    (net (code "84") (name "/~{EN}") (class "Default")
      (node (ref "U$1") (pin "28") (pinfunction "28_28") (pintype "bidirectional"))
      (node (ref "U1") (pin "9") (pinfunction "~{EN}_9") (pintype "input"))
    )
    (net (code "85") (name "/~{RST}") (class "Default")
      (node (ref "U$1") (pin "RESET") (pinfunction "RESET_RESET") (pintype "bidirectional"))
      (node (ref "U1") (pin "13") (pinfunction "~{RESET}_13") (pintype "input"))
      (node (ref "U2") (pin "15") (pinfunction "~{RST}_15") (pintype "input"))
    )
    (net (code "86") (name "/~{SLEEP}") (class "Default")
      (node (ref "U$1") (pin "39/A20") (pinfunction "39/A20_39/A20") (pintype "bidirectional"))
      (node (ref "U1") (pin "14") (pinfunction "~{SLEEP}_14") (pintype "input"))
    )
    (net (code "87") (name "GND") (class "Default")
      (node (ref "B1") (pin "-") (pinfunction "-_-") (pintype "passive"))
      (node (ref "B2") (pin "-") (pinfunction "-_-") (pintype "passive"))
      (node (ref "C10") (pin "2") (pinfunction "2_2") (pintype "passive"))
      (node (ref "C11") (pin "2") (pinfunction "2_2") (pintype "passive"))
      (node (ref "C12") (pin "2") (pinfunction "2_2") (pintype "passive"))
      (node (ref "C13") (pin "-") (pinfunction "-_-") (pintype "passive"))
      (node (ref "C14") (pin "2") (pinfunction "2_2") (pintype "passive"))
      (node (ref "C15") (pin "2") (pinfunction "2_2") (pintype "passive"))
      (node (ref "C16") (pin "2") (pinfunction "2_2") (pintype "passive"))
      (node (ref "C17") (pin "2") (pinfunction "2_2") (pintype "passive"))
      (node (ref "C18") (pin "2") (pinfunction "2_2") (pintype "passive"))
      (node (ref "C19") (pin "2") (pinfunction "2_2") (pintype "passive"))
      (node (ref "C2") (pin "2") (pinfunction "2_2") (pintype "passive"))
      (node (ref "C20") (pin "2") (pinfunction "2_2") (pintype "passive"))
      (node (ref "C21") (pin "-") (pinfunction "-_-") (pintype "passive"))
      (node (ref "C3") (pin "2") (pinfunction "2_2") (pintype "passive"))
      (node (ref "C4") (pin "-") (pinfunction "-_-") (pintype "passive"))
      (node (ref "C5") (pin "2") (pinfunction "2_2") (pintype "passive"))
      (node (ref "C6") (pin "-") (pinfunction "-_-") (pintype "passive"))
      (node (ref "C7") (pin "2") (pinfunction "2_2") (pintype "passive"))
      (node (ref "C8") (pin "-") (pinfunction "-_-") (pintype "passive"))
      (node (ref "C9") (pin "2") (pinfunction "2_2") (pintype "passive"))
      (node (ref "D10") (pin "1") (pinfunction "A1_1") (pintype "passive"))
      (node (ref "D11") (pin "1") (pinfunction "A1_1") (pintype "passive"))
      (node (ref "D13") (pin "1") (pinfunction "A1_1") (pintype "passive"))
      (node (ref "D3") (pin "A") (pinfunction "A_A") (pintype "passive"))
      (node (ref "D4") (pin "A") (pinfunction "A_A") (pintype "passive"))
      (node (ref "D5") (pin "A") (pinfunction "A_A") (pintype "passive"))
      (node (ref "D6") (pin "A") (pinfunction "A_A") (pintype "passive"))
      (node (ref "D9") (pin "1") (pinfunction "A1_1") (pintype "passive"))
      (node (ref "GND") (pin "TP") (pinfunction "TP_TP") (pintype "input"))
      (node (ref "IC1") (pin "12") (pinfunction "GND_12") (pintype "bidirectional"))
      (node (ref "IC1") (pin "13") (pinfunction "GND_13") (pintype "bidirectional"))
      (node (ref "IC1") (pin "4") (pinfunction "GND_4") (pintype "bidirectional"))
      (node (ref "IC1") (pin "5") (pinfunction "GND_5") (pintype "bidirectional"))
      (node (ref "IC2") (pin "12") (pinfunction "GND_12") (pintype "bidirectional"))
      (node (ref "IC2") (pin "13") (pinfunction "GND_13") (pintype "bidirectional"))
      (node (ref "IC2") (pin "4") (pinfunction "GND_4") (pintype "bidirectional"))
      (node (ref "IC2") (pin "5") (pinfunction "GND_5") (pintype "bidirectional"))
      (node (ref "IC3") (pin "12") (pinfunction "GND_12") (pintype "bidirectional"))
      (node (ref "IC3") (pin "13") (pinfunction "GND_13") (pintype "bidirectional"))
      (node (ref "IC3") (pin "4") (pinfunction "GND_4") (pintype "bidirectional"))
      (node (ref "IC3") (pin "5") (pinfunction "GND_5") (pintype "bidirectional"))
      (node (ref "IC4") (pin "12") (pinfunction "GND_12") (pintype "bidirectional"))
      (node (ref "IC4") (pin "13") (pinfunction "GND_13") (pintype "bidirectional"))
      (node (ref "IC4") (pin "4") (pinfunction "GND_4") (pintype "bidirectional"))
      (node (ref "IC4") (pin "5") (pinfunction "GND_5") (pintype "bidirectional"))
      (node (ref "IC5") (pin "9") (pinfunction "GND_9") (pintype "power_in"))
      (node (ref "J1") (pin "4") (pinfunction "4_4") (pintype "bidirectional"))
      (node (ref "J2") (pin "4") (pinfunction "4_4") (pintype "bidirectional"))
      (node (ref "J3") (pin "4") (pinfunction "4_4") (pintype "bidirectional"))
      (node (ref "JP3") (pin "4") (pinfunction "4_4") (pintype "passive"))
      (node (ref "JP3") (pin "9") (pinfunction "9_9") (pintype "passive"))
      (node (ref "LED3") (pin "K") (pinfunction "C_K") (pintype "passive"))
      (node (ref "MT1") (pin "1") (pinfunction "GND_1") (pintype "passive"))
      (node (ref "MT2") (pin "1") (pinfunction "GND_1") (pintype "passive"))
      (node (ref "OK1") (pin "5") (pinfunction "GND_5") (pintype "passive"))
      (node (ref "R10") (pin "1") (pinfunction "1_1") (pintype "passive"))
      (node (ref "R4") (pin "1") (pinfunction "1_1") (pintype "passive"))
      (node (ref "R6") (pin "1") (pinfunction "1_1") (pintype "passive"))
      (node (ref "R8") (pin "1") (pinfunction "1_1") (pintype "passive"))
      (node (ref "U$1") (pin "AGND") (pinfunction "AGND_AGND") (pintype "bidirectional"))
      (node (ref "U$1") (pin "GND") (pinfunction "GND_GND") (pintype "bidirectional"))
      (node (ref "U$1") (pin "GND2") (pinfunction "GND2_GND2") (pintype "bidirectional"))
      (node (ref "U$1") (pin "GND3") (pinfunction "GND3_GND3") (pintype "bidirectional"))
      (node (ref "U1") (pin "1") (pinfunction "GND_1") (pintype "passive"))
      (node (ref "U1") (pin "7") (pinfunction "GND2_7") (pintype "bidirectional"))
      (node (ref "U2") (pin "3") (pinfunction "A0_3") (pintype "input"))
      (node (ref "U2") (pin "4") (pinfunction "A1_4") (pintype "input"))
      (node (ref "U2") (pin "5") (pinfunction "A2_5") (pintype "input"))
      (node (ref "U2") (pin "8") (pinfunction "GND_8") (pintype "passive"))
      (node (ref "U3") (pin "GND") (pinfunction "GND_GND") (pintype "input"))
      (node (ref "X10") (pin "8") (pinfunction "K_8") (pintype "passive"))
      (node (ref "X11") (pin "8") (pinfunction "K_8") (pintype "passive"))
      (node (ref "X5") (pin "6") (pinfunction "K_6") (pintype "passive"))
    )
    (net (code "88") (name "Net-(B2-Pad+)") (class "Default")
      (node (ref "B2") (pin "+") (pinfunction "+_+") (pintype "passive"))
      (node (ref "C3") (pin "1") (pinfunction "1_1") (pintype "passive"))
      (node (ref "C8") (pin "+") (pinfunction "+_+") (pintype "passive"))
      (node (ref "JP1") (pin "2") (pinfunction "2_2") (pintype "passive"))
      (node (ref "U3") (pin "IN") (pinfunction "IN_IN") (pintype "input"))
    )
    (net (code "89") (name "Net-(C2-Pad1)") (class "Default")
      (node (ref "C2") (pin "1") (pinfunction "1_1") (pintype "passive"))
      (node (ref "C6") (pin "+") (pinfunction "+_+") (pintype "passive"))
      (node (ref "D1") (pin "A") (pinfunction "A_A") (pintype "passive"))
      (node (ref "D2") (pin "A") (pinfunction "A_A") (pintype "passive"))
      (node (ref "U3") (pin "OUT") (pinfunction "OUT_OUT") (pintype "passive"))
    )
    (net (code "90") (name "Net-(C5-Pad1)") (class "Default")
      (node (ref "C5") (pin "1") (pinfunction "1_1") (pintype "passive"))
      (node (ref "L1") (pin "2") (pinfunction "2_2") (pintype "passive"))
      (node (ref "U$1") (pin "AREF") (pinfunction "AREF_AREF") (pintype "bidirectional"))
    )
    (net (code "91") (name "Net-(D8-PadA)") (class "Default")
      (node (ref "D8") (pin "A") (pinfunction "A_A") (pintype "passive"))
      (node (ref "JP1") (pin "1") (pinfunction "1_1") (pintype "passive"))
    )
    (net (code "92") (name "Net-(IC5-CD+)") (class "Default")
      (node (ref "F1") (pin "2") (pinfunction "2_2") (pintype "passive"))
      (node (ref "IC5") (pin "10") (pinfunction "CD+_10") (pintype "passive"))
      (node (ref "X10") (pin "2") (pinfunction "K_2") (pintype "passive"))
      (node (ref "X10") (pin "4") (pinfunction "K_4") (pintype "passive"))
      (node (ref "X10") (pin "6") (pinfunction "K_6") (pintype "passive"))
      (node (ref "X11") (pin "2") (pinfunction "K_2") (pintype "passive"))
      (node (ref "X11") (pin "4") (pinfunction "K_4") (pintype "passive"))
      (node (ref "X11") (pin "6") (pinfunction "K_6") (pintype "passive"))
    )
    (net (code "93") (name "Net-(LED1-PadA)") (class "Default")
      (node (ref "LED1") (pin "A") (pinfunction "A_A") (pintype "passive"))
      (node (ref "R13") (pin "1") (pinfunction "1_1") (pintype "passive"))
    )
    (net (code "94") (name "Net-(LED2-PadA)") (class "Default")
      (node (ref "LED2") (pin "A") (pinfunction "A_A") (pintype "passive"))
      (node (ref "R14") (pin "1") (pinfunction "1_1") (pintype "passive"))
    )
    (net (code "95") (name "Net-(LED3-PadA)") (class "Default")
      (node (ref "LED3") (pin "A") (pinfunction "A_A") (pintype "passive"))
      (node (ref "R15") (pin "1") (pinfunction "1_1") (pintype "passive"))
    )
    (net (code "96") (name "Net-(LED4-PadA)") (class "Default")
      (node (ref "LED4") (pin "A") (pinfunction "A_A") (pintype "passive"))
      (node (ref "R18") (pin "1") (pinfunction "1_1") (pintype "passive"))
    )
    (net (code "97") (name "Net-(LED5-PadA)") (class "Default")
      (node (ref "LED5") (pin "A") (pinfunction "A_A") (pintype "passive"))
      (node (ref "R19") (pin "1") (pinfunction "1_1") (pintype "passive"))
    )
    (net (code "98") (name "Net-(LED6-PadA)") (class "Default")
      (node (ref "LED6") (pin "A") (pinfunction "A_A") (pintype "passive"))
      (node (ref "R20") (pin "1") (pinfunction "1_1") (pintype "passive"))
    )
    (net (code "99") (name "Net-(LED7-PadA)") (class "Default")
      (node (ref "LED7") (pin "A") (pinfunction "A_A") (pintype "passive"))
      (node (ref "R21") (pin "1") (pinfunction "1_1") (pintype "passive"))
    )
    (net (code "100") (name "Net-(LED8-PadA)") (class "Default")
      (node (ref "LED8") (pin "A") (pinfunction "A_A") (pintype "passive"))
      (node (ref "R22") (pin "1") (pinfunction "1_1") (pintype "passive"))
    )
    (net (code "101") (name "Net-(LED9-PadA)") (class "Default")
      (node (ref "LED9") (pin "A") (pinfunction "A_A") (pintype "passive"))
      (node (ref "R23") (pin "1") (pinfunction "1_1") (pintype "passive"))
    )
    (net (code "102") (name "Net-(LED10-PadA)") (class "Default")
      (node (ref "LED10") (pin "A") (pinfunction "A_A") (pintype "passive"))
      (node (ref "R24") (pin "1") (pinfunction "1_1") (pintype "passive"))
    )
    (net (code "103") (name "Net-(LED11-PadA)") (class "Default")
      (node (ref "LED11") (pin "A") (pinfunction "A_A") (pintype "passive"))
      (node (ref "R25") (pin "1") (pinfunction "1_1") (pintype "passive"))
    )
    (net (code "104") (name "Net-(LED12-PadA)") (class "Default")
      (node (ref "LED12") (pin "A") (pinfunction "A_A") (pintype "passive"))
      (node (ref "R26") (pin "1") (pinfunction "1_1") (pintype "passive"))
    )
    (net (code "105") (name "Net-(LED13-PadA)") (class "Default")
      (node (ref "LED13") (pin "A") (pinfunction "A_A") (pintype "passive"))
      (node (ref "R27") (pin "1") (pinfunction "1_1") (pintype "passive"))
    )
    (net (code "106") (name "Net-(LED14-PadA)") (class "Default")
      (node (ref "LED14") (pin "A") (pinfunction "A_A") (pintype "passive"))
      (node (ref "R28") (pin "1") (pinfunction "1_1") (pintype "passive"))
    )
    (net (code "107") (name "Net-(LED15-PadA)") (class "Default")
      (node (ref "LED15") (pin "A") (pinfunction "A_A") (pintype "passive"))
      (node (ref "R29") (pin "1") (pinfunction "1_1") (pintype "passive"))
    )
    (net (code "108") (name "Net-(LED16-PadA)") (class "Default")
      (node (ref "LED16") (pin "A") (pinfunction "A_A") (pintype "passive"))
      (node (ref "R30") (pin "1") (pinfunction "1_1") (pintype "passive"))
    )
    (net (code "109") (name "Net-(LED17-PadA)") (class "Default")
      (node (ref "LED17") (pin "A") (pinfunction "A_A") (pintype "passive"))
      (node (ref "R31") (pin "1") (pinfunction "1_1") (pintype "passive"))
    )
    (net (code "110") (name "Net-(LED18-PadA)") (class "Default")
      (node (ref "LED18") (pin "A") (pinfunction "A_A") (pintype "passive"))
      (node (ref "R32") (pin "1") (pinfunction "1_1") (pintype "passive"))
    )
    (net (code "111") (name "Net-(LED19-PadA)") (class "Default")
      (node (ref "LED19") (pin "A") (pinfunction "A_A") (pintype "passive"))
      (node (ref "R33") (pin "1") (pinfunction "1_1") (pintype "passive"))
    )
    (net (code "112") (name "Net-(OK1-A)") (class "Default")
      (node (ref "C1") (pin "1") (pinfunction "1_1") (pintype "passive"))
      (node (ref "D7") (pin "C") (pinfunction "C_C") (pintype "passive"))
      (node (ref "OK1") (pin "2") (pinfunction "A_2") (pintype "passive"))
      (node (ref "R1") (pin "1") (pinfunction "1_1") (pintype "passive"))
    )
    (net (code "113") (name "Net-(OK1-VCC)") (class "Default")
      (node (ref "C10") (pin "1") (pinfunction "1_1") (pintype "passive"))
      (node (ref "C11") (pin "1") (pinfunction "1_1") (pintype "passive"))
      (node (ref "D1") (pin "C") (pinfunction "C_C") (pintype "passive"))
      (node (ref "OK1") (pin "8") (pinfunction "VCC_8") (pintype "passive"))
      (node (ref "R2") (pin "2") (pinfunction "2_2") (pintype "passive"))
    )
    (net (code "114") (name "Net-(OK1-VE)") (class "Default")
      (node (ref "OK1") (pin "7") (pinfunction "VE_7") (pintype "passive"))
      (node (ref "R2") (pin "1") (pinfunction "1_1") (pintype "passive"))
    )
    (net (code "115") (name "Net-(Q1-PadB)") (class "Default")
      (node (ref "Q1") (pin "B") (pinfunction "B_B") (pintype "passive"))
      (node (ref "R5") (pin "1") (pinfunction "1_1") (pintype "passive"))
    )
    (net (code "116") (name "Net-(Q2-PadB)") (class "Default")
      (node (ref "Q2") (pin "B") (pinfunction "B_B") (pintype "passive"))
      (node (ref "R7") (pin "1") (pinfunction "1_1") (pintype "passive"))
    )
    (net (code "117") (name "Net-(Q3-PadB)") (class "Default")
      (node (ref "Q3") (pin "B") (pinfunction "B_B") (pintype "passive"))
      (node (ref "R9") (pin "1") (pinfunction "1_1") (pintype "passive"))
    )
    (net (code "118") (name "Net-(Q4-PadB)") (class "Default")
      (node (ref "Q4") (pin "B") (pinfunction "B_B") (pintype "passive"))
      (node (ref "R11") (pin "1") (pinfunction "1_1") (pintype "passive"))
    )
    (net (code "119") (name "Net-(U1-VMOT)") (class "Default")
      (node (ref "C21") (pin "+") (pinfunction "+_+") (pintype "passive"))
      (node (ref "D12") (pin "C") (pinfunction "C_C") (pintype "passive"))
      (node (ref "U1") (pin "8") (pinfunction "VMOT_8") (pintype "bidirectional"))
    )
    (net (code "120") (name "Net-(X1B-K)") (class "Default")
      (node (ref "D3") (pin "C") (pinfunction "C_C") (pintype "passive"))
      (node (ref "Q1") (pin "C") (pinfunction "C_C") (pintype "passive"))
      (node (ref "X1") (pin "2") (pinfunction "K_2") (pintype "passive"))
      (node (ref "X1") (pin "5") (pinfunction "K_5") (pintype "passive"))
    )
    (net (code "121") (name "Net-(X2B-K)") (class "Default")
      (node (ref "D4") (pin "C") (pinfunction "C_C") (pintype "passive"))
      (node (ref "Q2") (pin "C") (pinfunction "C_C") (pintype "passive"))
      (node (ref "X2") (pin "2") (pinfunction "K_2") (pintype "passive"))
      (node (ref "X2") (pin "5") (pinfunction "K_5") (pintype "passive"))
    )
    (net (code "122") (name "Net-(X3B-K)") (class "Default")
      (node (ref "D6") (pin "C") (pinfunction "C_C") (pintype "passive"))
      (node (ref "Q3") (pin "C") (pinfunction "C_C") (pintype "passive"))
      (node (ref "X3") (pin "2") (pinfunction "K_2") (pintype "passive"))
      (node (ref "X3") (pin "5") (pinfunction "K_5") (pintype "passive"))
    )
    (net (code "123") (name "Net-(X4B-K)") (class "Default")
      (node (ref "D5") (pin "C") (pinfunction "C_C") (pintype "passive"))
      (node (ref "Q4") (pin "C") (pinfunction "C_C") (pintype "passive"))
      (node (ref "X4") (pin "2") (pinfunction "K_2") (pintype "passive"))
      (node (ref "X4") (pin "5") (pinfunction "K_5") (pintype "passive"))
    )
    (net (code "124") (name "Net-(X5A-K)") (class "Default")
      (node (ref "D12") (pin "A") (pinfunction "A_A") (pintype "passive"))
      (node (ref "X5") (pin "1") (pinfunction "K_1") (pintype "passive"))
    )
    (net (code "125") (name "Net-(X9C-KL)") (class "Default")
      (node (ref "B1") (pin "AC1") (pinfunction "AC1_AC1") (pintype "passive"))
      (node (ref "X9") (pin "3") (pinfunction "KL_3") (pintype "passive"))
    )
    (net (code "126") (name "Net-(X9D-KL)") (class "Default")
      (node (ref "B1") (pin "AC2") (pinfunction "AC2_AC2") (pintype "passive"))
      (node (ref "X9") (pin "4") (pinfunction "KL_4") (pintype "passive"))
    )
    (net (code "127") (name "unconnected-(JP3-Pad8)") (class "Default")
      (node (ref "JP3") (pin "8") (pinfunction "8_8") (pintype "passive"))
    )
    (net (code "128") (name "unconnected-(U$1-PadPROG)") (class "Default")
      (node (ref "U$1") (pin "PROG") (pinfunction "PROG_PROG") (pintype "bidirectional"))
    )
    (net (code "129") (name "unconnected-(U$1-PadU5V)") (class "Default")
      (node (ref "U$1") (pin "U5V") (pinfunction "U5V_U5V") (pintype "bidirectional"))
    )
    (net (code "130") (name "unconnected-(U$1-PadUD+)") (class "Default")
      (node (ref "U$1") (pin "UD+") (pinfunction "UD+_UD+") (pintype "bidirectional"))
    )
    (net (code "131") (name "unconnected-(U$1-PadUD-)") (class "Default")
      (node (ref "U$1") (pin "UD-") (pinfunction "UD-_UD-") (pintype "bidirectional"))
    )
    (net (code "132") (name "unconnected-(U$1-PadUGND1)") (class "Default")
      (node (ref "U$1") (pin "UGND1") (pinfunction "UGND1_UGND1") (pintype "bidirectional"))
    )
    (net (code "133") (name "unconnected-(U$1-PadUGND2)") (class "Default")
      (node (ref "U$1") (pin "UGND2") (pinfunction "UGND2_UGND2") (pintype "bidirectional"))
    )
    (net (code "134") (name "unconnected-(U$1-PadVBAT)") (class "Default")
      (node (ref "U$1") (pin "VBAT") (pinfunction "VBAT_VBAT") (pintype "bidirectional"))
    )
    (net (code "135") (name "unconnected-(U$1-PadVUSB)") (class "Default")
      (node (ref "U$1") (pin "VUSB") (pinfunction "VUSB_VUSB") (pintype "bidirectional"))
    )
  )
)
